# CH32F203RBT6-R0.net
KiCad netlist of a schematic drawn in Altium Designer
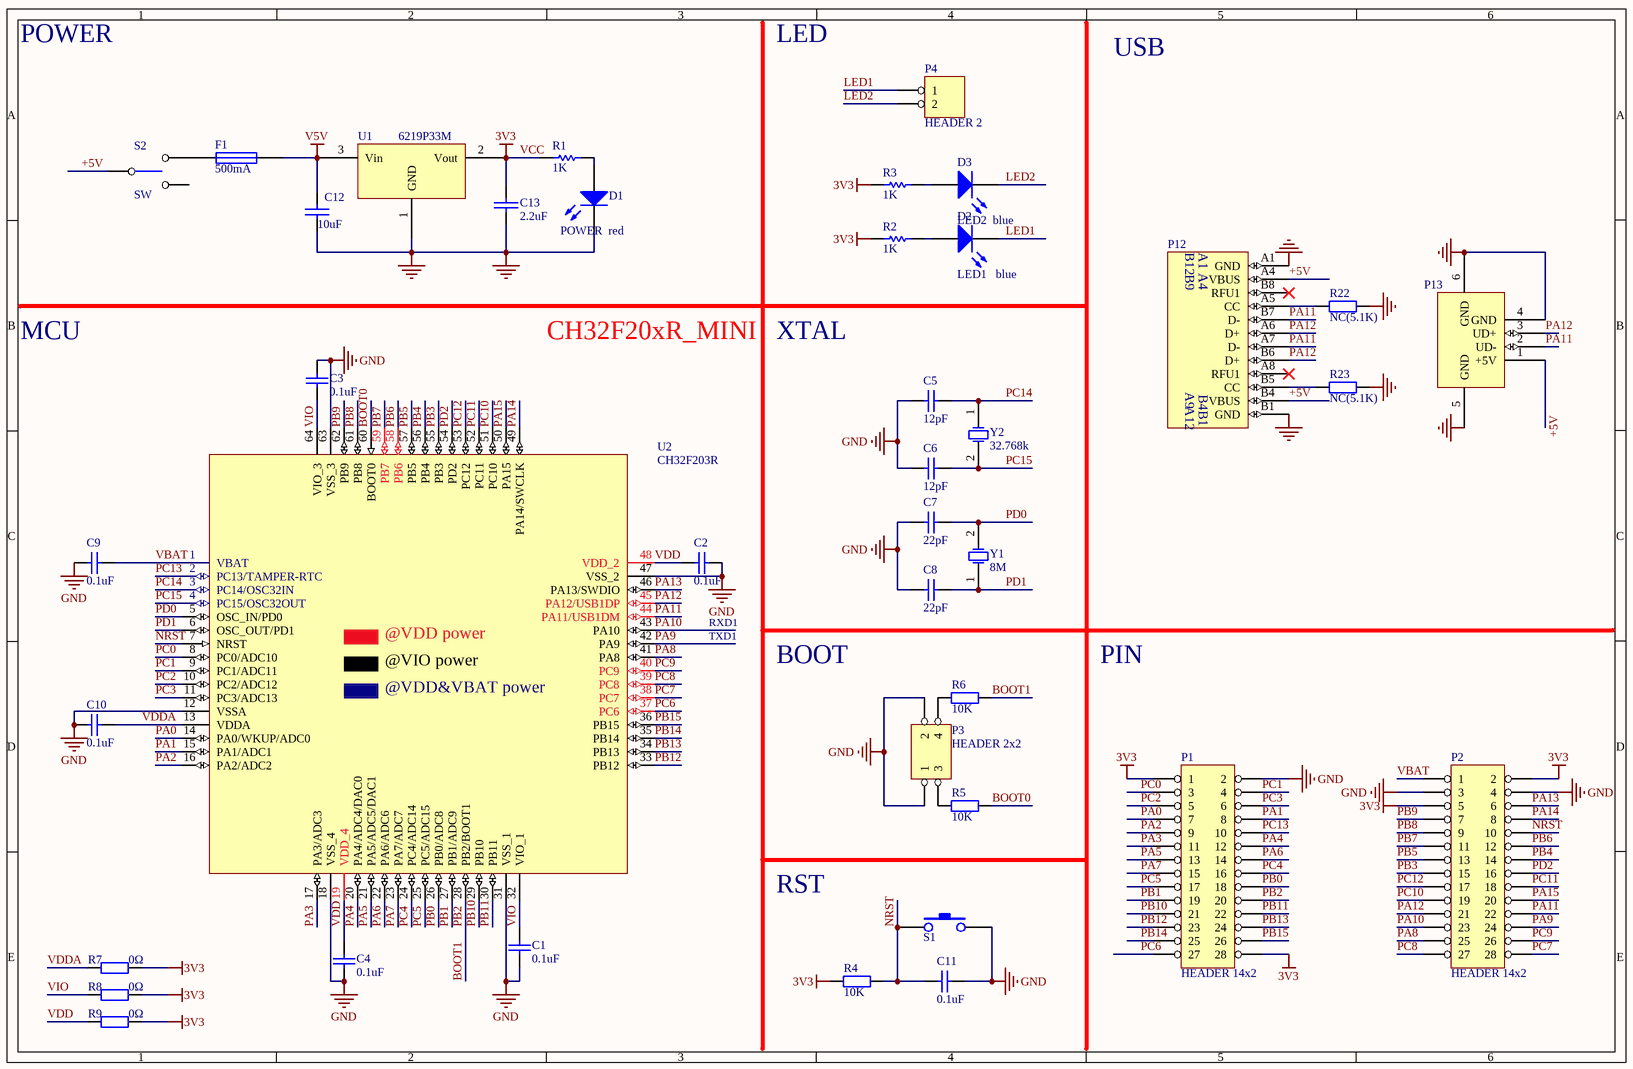
[diagram p0: CH32F203RBT6-R0.SchDoc]

(export (version "E")
  (design (tool "Eeschema 10.0.6"))
  (components
    (comp (ref "C1")
      (value "0.1uF")
      (footprint "0603_C")
      (description "Capacitor")
      (fields (field (name "PUBLISHER") "Altium Limited"))
      (libsource (lib "Miscellaneous Devices") (part "Cap"))
    )
    (comp (ref "C2")
      (value "0.1uF")
      (footprint "0603_C")
      (description "Capacitor")
      (fields (field (name "PUBLISHER") "Altium Limited"))
      (libsource (lib "Miscellaneous Devices") (part "Cap"))
    )
    (comp (ref "C3")
      (value "0.1uF")
      (footprint "0603_C")
      (description "Capacitor")
      (fields (field (name "PUBLISHER") "Altium Limited"))
      (libsource (lib "Miscellaneous Devices") (part "Cap"))
    )
    (comp (ref "C4")
      (value "0.1uF")
      (footprint "0603_C")
      (description "Capacitor")
      (fields (field (name "PUBLISHER") "Altium Limited"))
      (libsource (lib "Miscellaneous Devices") (part "Cap"))
    )
    (comp (ref "C5")
      (value "12pF")
      (footprint "0603_C")
      (description "Capacitor")
      (fields (field (name "PUBLISHER") "Altium Limited"))
      (libsource (lib "Miscellaneous Devices") (part "Cap"))
    )
    (comp (ref "C6")
      (value "12pF")
      (footprint "0603_C")
      (description "Capacitor")
      (fields (field (name "PUBLISHER") "Altium Limited"))
      (libsource (lib "Miscellaneous Devices") (part "Cap"))
    )
    (comp (ref "C7")
      (value "22pF")
      (footprint "0603_C")
      (description "Capacitor")
      (fields (field (name "PUBLISHER") "Altium Limited"))
      (libsource (lib "Miscellaneous Devices") (part "Cap"))
    )
    (comp (ref "C8")
      (value "22pF")
      (footprint "0603_C")
      (description "Capacitor")
      (fields (field (name "PUBLISHER") "Altium Limited"))
      (libsource (lib "Miscellaneous Devices") (part "Cap"))
    )
    (comp (ref "C9")
      (value "0.1uF")
      (footprint "0603_C")
      (description "Capacitor")
      (fields (field (name "PUBLISHER") "Altium Limited"))
      (libsource (lib "Miscellaneous Devices") (part "Cap"))
    )
    (comp (ref "C10")
      (value "0.1uF")
      (footprint "0603_C")
      (description "Capacitor")
      (fields (field (name "PUBLISHER") "Altium Limited"))
      (libsource (lib "Miscellaneous Devices") (part "Cap"))
    )
    (comp (ref "C11")
      (value "0.1uF")
      (footprint "0603_C")
      (description "Capacitor")
      (fields (field (name "PUBLISHER") "Altium Limited"))
      (libsource (lib "Miscellaneous Devices") (part "Cap"))
    )
    (comp (ref "C12")
      (value "10uF")
      (footprint "3216_C")
      (description "Capacitor")
      (libsource (lib "*") (part "CAP"))
    )
    (comp (ref "C13")
      (value "2.2uF")
      (footprint "0603_C")
      (description "Capacitor")
      (libsource (lib "*") (part "CAP"))
    )
    (comp (ref "D1")
      (value "POWER  red")
      (footprint "0603+")
      (description "Typical INFRARED GaAs LED")
      (fields (field (name "PUBLISHER") "Altium Limited"))
      (libsource (lib "Miscellaneous Devices") (part "LED0"))
    )
    (comp (ref "D2")
      (value "LED1   blue")
      (footprint "0603+")
      (description "Typical INFRARED GaAs LED")
      (fields (field (name "PUBLISHER") "Altium Limited"))
      (libsource (lib "Miscellaneous Devices") (part "LED0"))
    )
    (comp (ref "D3")
      (value "LED2  blue")
      (footprint "0603+")
      (description "Typical INFRARED GaAs LED")
      (fields (field (name "PUBLISHER") "Altium Limited"))
      (libsource (lib "Miscellaneous Devices") (part "LED0"))
    )
    (comp (ref "F1")
      (value "500mA")
      (footprint "0603")
      (description "Fuse")
      (libsource (lib "*") (part "FUSE1"))
    )
    (comp (ref "P1")
      (value "HEADER 14x2")
      (footprint "MYPCB:IDC28-2.54MM")
      (description "Header, 14-Pin, Dual row")
      (libsource (lib "wch_sch_others") (part "HEADER 14x2"))
    )
    (comp (ref "P2")
      (value "HEADER 14x2")
      (footprint "MYPCB:IDC28-2.54MM")
      (description "Header, 14-Pin, Dual row")
      (libsource (lib "wch_sch_others") (part "HEADER 14x2"))
    )
    (comp (ref "P3")
      (value "HEADER 2x2")
      (footprint "MYPCB:IDC4-2.54MM")
      (description "Header, 2-Pin, Dual row")
      (libsource (lib "wch_sch_others") (part "HEADER 2x2"))
    )
    (comp (ref "P4")
      (value "HEADER 2")
      (footprint "MYPCB:SIP2-2.54mm")
      (description "Header, 2-Pin")
      (libsource (lib "wch_sch_others") (part "HEADER 2"))
    )
    (comp (ref "P12")
      (value "TYPE-C")
      (footprint "TYPE-C-Receptacle-2.0")
      (libsource (lib "*") (part "TYPE-C1"))
    )
    (comp (ref "P13")
      (value "USB_A")
      (footprint "USBAF")
      (description "USB Port")
      (libsource (lib "CHXXXSCH") (part "USB"))
    )
    (comp (ref "R1")
      (value "1K")
      (footprint "0603")
      (description "Semiconductor Resistor")
      (fields (field (name "PUBLISHER") "Altium Limited"))
      (libsource (lib "Miscellaneous Devices") (part "Res Semi"))
    )
    (comp (ref "R2")
      (value "1K")
      (footprint "0603")
      (description "Semiconductor Resistor")
      (fields (field (name "PUBLISHER") "Altium Limited"))
      (libsource (lib "Miscellaneous Devices") (part "Res Semi"))
    )
    (comp (ref "R3")
      (value "1K")
      (footprint "0603")
      (description "Semiconductor Resistor")
      (fields (field (name "PUBLISHER") "Altium Limited"))
      (libsource (lib "Miscellaneous Devices") (part "Res Semi"))
    )
    (comp (ref "R4")
      (value "10K")
      (footprint "0603")
      (description "Resistor")
      (fields (field (name "PUBLISHER") "Altium Limited"))
      (libsource (lib "Miscellaneous Devices") (part "Res2"))
    )
    (comp (ref "R5")
      (value "10K")
      (footprint "0603")
      (description "Resistor")
      (fields (field (name "PUBLISHER") "Altium Limited"))
      (libsource (lib "Miscellaneous Devices") (part "Res2"))
    )
    (comp (ref "R6")
      (value "10K")
      (footprint "0603")
      (description "Resistor")
      (fields (field (name "PUBLISHER") "Altium Limited"))
      (libsource (lib "Miscellaneous Devices") (part "Res2"))
    )
    (comp (ref "R7")
      (value "0Ω")
      (footprint "0603")
      (description "Resistor")
      (fields (field (name "PUBLISHER") "Altium Limited"))
      (libsource (lib "Miscellaneous Devices") (part "Res2"))
    )
    (comp (ref "R8")
      (value "0Ω")
      (footprint "0603")
      (description "Resistor")
      (fields (field (name "PUBLISHER") "Altium Limited"))
      (libsource (lib "Miscellaneous Devices") (part "Res2"))
    )
    (comp (ref "R9")
      (value "0Ω")
      (footprint "0603")
      (description "Resistor")
      (fields (field (name "PUBLISHER") "Altium Limited"))
      (libsource (lib "Miscellaneous Devices") (part "Res2"))
    )
    (comp (ref "R22")
      (value "NC(5.1K)")
      (footprint "0603")
      (description "Resistor")
      (libsource (lib "") (part "Res2_1"))
    )
    (comp (ref "R23")
      (value "NC(5.1K)")
      (footprint "0603")
      (description "Resistor")
      (libsource (lib "") (part "Res2_1"))
    )
    (comp (ref "S1")
      (value "RST")
      (footprint "SMD_6.1x3.65x2.5mm-KEY")
      (libsource (lib "CCDXPLIB") (part "KEY"))
    )
    (comp (ref "S2") (value "SW") (footprint "KEY2") (libsource (lib "MYSCH") (part "SW")))
    (comp (ref "U1")
      (value "6219P33M")
      (footprint "SOT-23")
      (libsource (lib "wch_sch_others") (part "6219P33M"))
    )
    (comp (ref "U2")
      (value "CH32F203R")
      (footprint "LQFP64M_10x10")
      (description "ARM M3 HD-MCU, 144MHz, 8*UART, 10*Timer, 4*OPA")
      (libsource (lib "CHXXX") (part "CH32F203R"))
    )
    (comp (ref "Y1")
      (value "8M")
      (footprint "XT_AT49")
      (description "Crystal Oscillator")
      (fields (field (name "PUBLISHER") "Altium Limited"))
      (libsource (lib "Miscellaneous Devices") (part "XTAL"))
    )
    (comp (ref "Y2")
      (value "32.768k")
      (footprint "FC-135")
      (description "Crystal Oscillator")
      (fields (field (name "PUBLISHER") "Altium Limited"))
      (libsource (lib "Miscellaneous Devices") (part "XTAL"))
    )
  )
  (nets
    (net (code "1") (name "/+5V") (class "Default")
      (node (ref "P12") (pin "A4") (pinfunction "VBUS_A4") (pintype "bidirectional"))
      (node (ref "P12") (pin "B4") (pinfunction "VBUS_B4") (pintype "bidirectional"))
      (node (ref "P13") (pin "1") (pinfunction "+5V_1") (pintype "power_in"))
      (node (ref "S2") (pin "1") (pinfunction "1_1") (pintype "passive"))
    )
    (net (code "3") (name "/BOOT0") (class "Default")
      (node (ref "R5") (pin "1") (pinfunction "1_1") (pintype "passive"))
      (node (ref "U2") (pin "60") (pinfunction "BOOT0_60") (pintype "input"))
    )
    (net (code "4") (name "/BOOT1") (class "Default")
      (node (ref "P1") (pin "20") (pinfunction "20_20") (pintype "passive"))
      (node (ref "R6") (pin "1") (pinfunction "1_1") (pintype "passive"))
      (node (ref "U2") (pin "28") (pinfunction "PB2/BOOT1_28") (pintype "bidirectional"))
    )
    (net (code "5") (name "/LED1") (class "Default")
      (node (ref "D2") (pin "2") (pinfunction "K_2") (pintype "passive"))
      (node (ref "P4") (pin "1") (pinfunction "1_1") (pintype "passive"))
    )
    (net (code "6") (name "/LED2") (class "Default")
      (node (ref "D3") (pin "2") (pinfunction "K_2") (pintype "passive"))
      (node (ref "P4") (pin "2") (pinfunction "2_2") (pintype "passive"))
    )
    (net (code "7") (name "/NRST") (class "Default")
      (node (ref "C11") (pin "2") (pinfunction "2_2") (pintype "passive"))
      (node (ref "P2") (pin "10") (pinfunction "10_10") (pintype "passive"))
      (node (ref "R4") (pin "1") (pinfunction "1_1") (pintype "passive"))
      (node (ref "S1") (pin "1") (pinfunction "1_1") (pintype "passive"))
      (node (ref "U2") (pin "7") (pinfunction "NRST_7") (pintype "input"))
    )
    (net (code "8") (name "/PA0") (class "Default")
      (node (ref "P1") (pin "7") (pinfunction "7_7") (pintype "passive"))
      (node (ref "U2") (pin "14") (pinfunction "PA0/WKUP/ADC0_14") (pintype "bidirectional"))
    )
    (net (code "9") (name "/PA1") (class "Default")
      (node (ref "P1") (pin "8") (pinfunction "8_8") (pintype "passive"))
      (node (ref "U2") (pin "15") (pinfunction "PA1/ADC1_15") (pintype "bidirectional"))
    )
    (net (code "10") (name "/PA2") (class "Default")
      (node (ref "P1") (pin "9") (pinfunction "9_9") (pintype "passive"))
      (node (ref "U2") (pin "16") (pinfunction "PA2/ADC2_16") (pintype "bidirectional"))
    )
    (net (code "11") (name "/PA3") (class "Default")
      (node (ref "P1") (pin "11") (pinfunction "11_11") (pintype "passive"))
      (node (ref "U2") (pin "17") (pinfunction "PA3/ADC3_17") (pintype "bidirectional"))
    )
    (net (code "12") (name "/PA4") (class "Default")
      (node (ref "P1") (pin "12") (pinfunction "12_12") (pintype "passive"))
      (node (ref "U2") (pin "20") (pinfunction "PA4/ADC4/DAC0_20") (pintype "bidirectional"))
    )
    (net (code "13") (name "/PA5") (class "Default")
      (node (ref "P1") (pin "13") (pinfunction "13_13") (pintype "passive"))
      (node (ref "U2") (pin "21") (pinfunction "PA5/ADC5/DAC1_21") (pintype "bidirectional"))
    )
    (net (code "14") (name "/PA6") (class "Default")
      (node (ref "P1") (pin "14") (pinfunction "14_14") (pintype "passive"))
      (node (ref "U2") (pin "22") (pinfunction "PA6/ADC6_22") (pintype "bidirectional"))
    )
    (net (code "15") (name "/PA7") (class "Default")
      (node (ref "P1") (pin "15") (pinfunction "15_15") (pintype "passive"))
      (node (ref "U2") (pin "23") (pinfunction "PA7/ADC7_23") (pintype "bidirectional"))
    )
    (net (code "16") (name "/PA8") (class "Default")
      (node (ref "P2") (pin "25") (pinfunction "25_25") (pintype "passive"))
      (node (ref "U2") (pin "41") (pinfunction "PA8_41") (pintype "bidirectional"))
    )
    (net (code "17") (name "/PA9") (class "Default")
      (node (ref "P2") (pin "24") (pinfunction "24_24") (pintype "passive"))
      (node (ref "U2") (pin "42") (pinfunction "PA9_42") (pintype "bidirectional"))
    )
    (net (code "18") (name "/PA10") (class "Default")
      (node (ref "P2") (pin "23") (pinfunction "23_23") (pintype "passive"))
      (node (ref "U2") (pin "43") (pinfunction "PA10_43") (pintype "bidirectional"))
    )
    (net (code "19") (name "/PA11") (class "Default")
      (node (ref "P12") (pin "A7") (pinfunction "D-_A7") (pintype "bidirectional"))
      (node (ref "P12") (pin "B7") (pinfunction "D-_B7") (pintype "bidirectional"))
      (node (ref "P13") (pin "2") (pinfunction "UD-_2") (pintype "bidirectional"))
      (node (ref "P2") (pin "22") (pinfunction "22_22") (pintype "passive"))
      (node (ref "U2") (pin "44") (pinfunction "PA11/USB1DM_44") (pintype "bidirectional"))
    )
    (net (code "20") (name "/PA12") (class "Default")
      (node (ref "P12") (pin "A6") (pinfunction "D+_A6") (pintype "bidirectional"))
      (node (ref "P12") (pin "B6") (pinfunction "D+_B6") (pintype "bidirectional"))
      (node (ref "P13") (pin "3") (pinfunction "UD+_3") (pintype "bidirectional"))
      (node (ref "P2") (pin "21") (pinfunction "21_21") (pintype "passive"))
      (node (ref "U2") (pin "45") (pinfunction "PA12/USB1DP_45") (pintype "bidirectional"))
    )
    (net (code "21") (name "/PA13") (class "Default")
      (node (ref "P2") (pin "6") (pinfunction "6_6") (pintype "passive"))
      (node (ref "U2") (pin "46") (pinfunction "PA13/SWDIO_46") (pintype "bidirectional"))
    )
    (net (code "22") (name "/PA14") (class "Default")
      (node (ref "P2") (pin "8") (pinfunction "8_8") (pintype "passive"))
      (node (ref "U2") (pin "49") (pinfunction "PA14/SWCLK_49") (pintype "bidirectional"))
    )
    (net (code "23") (name "/PA15") (class "Default")
      (node (ref "P2") (pin "20") (pinfunction "20_20") (pintype "passive"))
      (node (ref "U2") (pin "50") (pinfunction "PA15_50") (pintype "bidirectional"))
    )
    (net (code "24") (name "/PB0") (class "Default")
      (node (ref "P1") (pin "18") (pinfunction "18_18") (pintype "passive"))
      (node (ref "U2") (pin "26") (pinfunction "PB0/ADC8_26") (pintype "bidirectional"))
    )
    (net (code "25") (name "/PB1") (class "Default")
      (node (ref "P1") (pin "19") (pinfunction "19_19") (pintype "passive"))
      (node (ref "U2") (pin "27") (pinfunction "PB1/ADC9_27") (pintype "bidirectional"))
    )
    (net (code "26") (name "/PB3") (class "Default")
      (node (ref "P2") (pin "15") (pinfunction "15_15") (pintype "passive"))
      (node (ref "U2") (pin "55") (pinfunction "PB3_55") (pintype "bidirectional"))
    )
    (net (code "27") (name "/PB4") (class "Default")
      (node (ref "P2") (pin "14") (pinfunction "14_14") (pintype "passive"))
      (node (ref "U2") (pin "56") (pinfunction "PB4_56") (pintype "bidirectional"))
    )
    (net (code "28") (name "/PB5") (class "Default")
      (node (ref "P2") (pin "13") (pinfunction "13_13") (pintype "passive"))
      (node (ref "U2") (pin "57") (pinfunction "PB5_57") (pintype "bidirectional"))
    )
    (net (code "29") (name "/PB6") (class "Default")
      (node (ref "P2") (pin "12") (pinfunction "12_12") (pintype "passive"))
      (node (ref "U2") (pin "58") (pinfunction "PB6_58") (pintype "bidirectional"))
    )
    (net (code "30") (name "/PB7") (class "Default")
      (node (ref "P2") (pin "11") (pinfunction "11_11") (pintype "passive"))
      (node (ref "U2") (pin "59") (pinfunction "PB7_59") (pintype "bidirectional"))
    )
    (net (code "31") (name "/PB8") (class "Default")
      (node (ref "P2") (pin "9") (pinfunction "9_9") (pintype "passive"))
      (node (ref "U2") (pin "61") (pinfunction "PB8_61") (pintype "bidirectional"))
    )
    (net (code "32") (name "/PB9") (class "Default")
      (node (ref "P2") (pin "7") (pinfunction "7_7") (pintype "passive"))
      (node (ref "U2") (pin "62") (pinfunction "PB9_62") (pintype "bidirectional"))
    )
    (net (code "33") (name "/PB10") (class "Default")
      (node (ref "P1") (pin "21") (pinfunction "21_21") (pintype "passive"))
      (node (ref "U2") (pin "29") (pinfunction "PB10_29") (pintype "bidirectional"))
    )
    (net (code "34") (name "/PB11") (class "Default")
      (node (ref "P1") (pin "22") (pinfunction "22_22") (pintype "passive"))
      (node (ref "U2") (pin "30") (pinfunction "PB11_30") (pintype "bidirectional"))
    )
    (net (code "35") (name "/PB12") (class "Default")
      (node (ref "P1") (pin "23") (pinfunction "23_23") (pintype "passive"))
      (node (ref "U2") (pin "33") (pinfunction "PB12_33") (pintype "bidirectional"))
    )
    (net (code "36") (name "/PB13") (class "Default")
      (node (ref "P1") (pin "24") (pinfunction "24_24") (pintype "passive"))
      (node (ref "U2") (pin "34") (pinfunction "PB13_34") (pintype "bidirectional"))
    )
    (net (code "37") (name "/PB14") (class "Default")
      (node (ref "P1") (pin "25") (pinfunction "25_25") (pintype "passive"))
      (node (ref "U2") (pin "35") (pinfunction "PB14_35") (pintype "bidirectional"))
    )
    (net (code "38") (name "/PB15") (class "Default")
      (node (ref "P1") (pin "26") (pinfunction "26_26") (pintype "passive"))
      (node (ref "U2") (pin "36") (pinfunction "PB15_36") (pintype "bidirectional"))
    )
    (net (code "39") (name "/PC0") (class "Default")
      (node (ref "P1") (pin "3") (pinfunction "3_3") (pintype "passive"))
      (node (ref "U2") (pin "8") (pinfunction "PC0/ADC10_8") (pintype "bidirectional"))
    )
    (net (code "40") (name "/PC1") (class "Default")
      (node (ref "P1") (pin "4") (pinfunction "4_4") (pintype "passive"))
      (node (ref "U2") (pin "9") (pinfunction "PC1/ADC11_9") (pintype "bidirectional"))
    )
    (net (code "41") (name "/PC2") (class "Default")
      (node (ref "P1") (pin "5") (pinfunction "5_5") (pintype "passive"))
      (node (ref "U2") (pin "10") (pinfunction "PC2/ADC12_10") (pintype "bidirectional"))
    )
    (net (code "42") (name "/PC3") (class "Default")
      (node (ref "P1") (pin "6") (pinfunction "6_6") (pintype "passive"))
      (node (ref "U2") (pin "11") (pinfunction "PC3/ADC13_11") (pintype "bidirectional"))
    )
    (net (code "43") (name "/PC4") (class "Default")
      (node (ref "P1") (pin "16") (pinfunction "16_16") (pintype "passive"))
      (node (ref "U2") (pin "24") (pinfunction "PC4/ADC14_24") (pintype "bidirectional"))
    )
    (net (code "44") (name "/PC5") (class "Default")
      (node (ref "P1") (pin "17") (pinfunction "17_17") (pintype "passive"))
      (node (ref "U2") (pin "25") (pinfunction "PC5/ADC15_25") (pintype "bidirectional"))
    )
    (net (code "45") (name "/PC6") (class "Default")
      (node (ref "P1") (pin "27") (pinfunction "27_27") (pintype "passive"))
      (node (ref "U2") (pin "37") (pinfunction "PC6_37") (pintype "bidirectional"))
    )
    (net (code "46") (name "/PC7") (class "Default")
      (node (ref "P2") (pin "28") (pinfunction "28_28") (pintype "passive"))
      (node (ref "U2") (pin "38") (pinfunction "PC7_38") (pintype "bidirectional"))
    )
    (net (code "47") (name "/PC8") (class "Default")
      (node (ref "P2") (pin "27") (pinfunction "27_27") (pintype "passive"))
      (node (ref "U2") (pin "39") (pinfunction "PC8_39") (pintype "bidirectional"))
    )
    (net (code "48") (name "/PC9") (class "Default")
      (node (ref "P2") (pin "26") (pinfunction "26_26") (pintype "passive"))
      (node (ref "U2") (pin "40") (pinfunction "PC9_40") (pintype "bidirectional"))
    )
    (net (code "49") (name "/PC10") (class "Default")
      (node (ref "P2") (pin "19") (pinfunction "19_19") (pintype "passive"))
      (node (ref "U2") (pin "51") (pinfunction "PC10_51") (pintype "bidirectional"))
    )
    (net (code "50") (name "/PC11") (class "Default")
      (node (ref "P2") (pin "18") (pinfunction "18_18") (pintype "passive"))
      (node (ref "U2") (pin "52") (pinfunction "PC11_52") (pintype "bidirectional"))
    )
    (net (code "51") (name "/PC12") (class "Default")
      (node (ref "P2") (pin "17") (pinfunction "17_17") (pintype "passive"))
      (node (ref "U2") (pin "53") (pinfunction "PC12_53") (pintype "bidirectional"))
    )
    (net (code "52") (name "/PC13") (class "Default")
      (node (ref "P1") (pin "10") (pinfunction "10_10") (pintype "passive"))
      (node (ref "U2") (pin "2") (pinfunction "PC13/TAMPER-RTC_2") (pintype "bidirectional"))
    )
    (net (code "53") (name "/PC14") (class "Default")
      (node (ref "C5") (pin "1") (pinfunction "1_1") (pintype "passive"))
      (node (ref "U2") (pin "3") (pinfunction "PC14/OSC32IN_3") (pintype "bidirectional"))
      (node (ref "Y2") (pin "1") (pinfunction "OSC1_1") (pintype "passive"))
    )
    (net (code "54") (name "/PC15") (class "Default")
      (node (ref "C6") (pin "1") (pinfunction "1_1") (pintype "passive"))
      (node (ref "U2") (pin "4") (pinfunction "PC15/OSC32OUT_4") (pintype "bidirectional"))
      (node (ref "Y2") (pin "2") (pinfunction "OSC2_2") (pintype "passive"))
    )
    (net (code "55") (name "/PD0") (class "Default")
      (node (ref "C7") (pin "2") (pinfunction "2_2") (pintype "passive"))
      (node (ref "U2") (pin "5") (pinfunction "OSC_IN/PD0_5") (pintype "bidirectional"))
      (node (ref "Y1") (pin "2") (pinfunction "OSC2_2") (pintype "passive"))
    )
    (net (code "56") (name "/PD1") (class "Default")
      (node (ref "C8") (pin "2") (pinfunction "2_2") (pintype "passive"))
      (node (ref "U2") (pin "6") (pinfunction "OSC_OUT/PD1_6") (pintype "bidirectional"))
      (node (ref "Y1") (pin "1") (pinfunction "OSC1_1") (pintype "passive"))
    )
    (net (code "57") (name "/PD2") (class "Default")
      (node (ref "P2") (pin "16") (pinfunction "16_16") (pintype "passive"))
      (node (ref "U2") (pin "54") (pinfunction "PD2_54") (pintype "bidirectional"))
    )
    (net (code "58") (name "/VBAT") (class "Default")
      (node (ref "C9") (pin "1") (pinfunction "1_1") (pintype "passive"))
      (node (ref "P2") (pin "1") (pinfunction "1_1") (pintype "passive"))
      (node (ref "U2") (pin "1") (pinfunction "VBAT_1") (pintype "power_in"))
    )
    (net (code "59") (name "/VDD") (class "Default")
      (node (ref "C2") (pin "2") (pinfunction "2_2") (pintype "passive"))
      (node (ref "C4") (pin "2") (pinfunction "2_2") (pintype "passive"))
      (node (ref "R9") (pin "2") (pinfunction "2_2") (pintype "passive"))
      (node (ref "U2") (pin "19") (pinfunction "VDD_4_19") (pintype "power_in"))
      (node (ref "U2") (pin "48") (pinfunction "VDD_2_48") (pintype "power_in"))
    )
    (net (code "60") (name "/VDDA") (class "Default")
      (node (ref "C10") (pin "1") (pinfunction "1_1") (pintype "passive"))
      (node (ref "R7") (pin "2") (pinfunction "2_2") (pintype "passive"))
      (node (ref "U2") (pin "13") (pinfunction "VDDA_13") (pintype "power_in"))
    )
    (net (code "61") (name "/VIO") (class "Default")
      (node (ref "C1") (pin "2") (pinfunction "2_2") (pintype "passive"))
      (node (ref "C3") (pin "2") (pinfunction "2_2") (pintype "passive"))
      (node (ref "R8") (pin "2") (pinfunction "2_2") (pintype "passive"))
      (node (ref "U2") (pin "32") (pinfunction "VIO_1_32") (pintype "power_in"))
      (node (ref "U2") (pin "64") (pinfunction "VIO_3_64") (pintype "power_in"))
    )
    (net (code "62") (name "3V3") (class "Default")
      (node (ref "C13") (pin "1") (pinfunction "1_1") (pintype "passive"))
      (node (ref "P1") (pin "1") (pinfunction "1_1") (pintype "passive"))
      (node (ref "P1") (pin "28") (pinfunction "28_28") (pintype "passive"))
      (node (ref "P2") (pin "2") (pinfunction "2_2") (pintype "passive"))
      (node (ref "P2") (pin "5") (pinfunction "5_5") (pintype "passive"))
      (node (ref "R1") (pin "2") (pinfunction "2_2") (pintype "passive"))
      (node (ref "R2") (pin "1") (pinfunction "1_1") (pintype "passive"))
      (node (ref "R3") (pin "1") (pinfunction "1_1") (pintype "passive"))
      (node (ref "R4") (pin "2") (pinfunction "2_2") (pintype "passive"))
      (node (ref "R7") (pin "1") (pinfunction "1_1") (pintype "passive"))
      (node (ref "R8") (pin "1") (pinfunction "1_1") (pintype "passive"))
      (node (ref "R9") (pin "1") (pinfunction "1_1") (pintype "passive"))
      (node (ref "U1") (pin "2") (pinfunction "Vout_2") (pintype "passive"))
    )
    (net (code "63") (name "GND") (class "Default")
      (node (ref "C1") (pin "1") (pinfunction "1_1") (pintype "passive"))
      (node (ref "C10") (pin "2") (pinfunction "2_2") (pintype "passive"))
      (node (ref "C11") (pin "1") (pinfunction "1_1") (pintype "passive"))
      (node (ref "C12") (pin "2") (pinfunction "2_2") (pintype "passive"))
      (node (ref "C13") (pin "2") (pinfunction "2_2") (pintype "passive"))
      (node (ref "C2") (pin "1") (pinfunction "1_1") (pintype "passive"))
      (node (ref "C3") (pin "1") (pinfunction "1_1") (pintype "passive"))
      (node (ref "C4") (pin "1") (pinfunction "1_1") (pintype "passive"))
      (node (ref "C5") (pin "2") (pinfunction "2_2") (pintype "passive"))
      (node (ref "C6") (pin "2") (pinfunction "2_2") (pintype "passive"))
      (node (ref "C7") (pin "1") (pinfunction "1_1") (pintype "passive"))
      (node (ref "C8") (pin "1") (pinfunction "1_1") (pintype "passive"))
      (node (ref "C9") (pin "2") (pinfunction "2_2") (pintype "passive"))
      (node (ref "D1") (pin "2") (pinfunction "K_2") (pintype "passive"))
      (node (ref "P1") (pin "2") (pinfunction "2_2") (pintype "passive"))
      (node (ref "P12") (pin "A1") (pinfunction "GND_A1") (pintype "bidirectional"))
      (node (ref "P12") (pin "B1") (pinfunction "GND_B1") (pintype "bidirectional"))
      (node (ref "P13") (pin "4") (pinfunction "GND_4") (pintype "power_in"))
      (node (ref "P13") (pin "5") (pinfunction "GND_5") (pintype "power_in"))
      (node (ref "P13") (pin "6") (pinfunction "GND_6") (pintype "power_in"))
      (node (ref "P2") (pin "3") (pinfunction "3_3") (pintype "passive"))
      (node (ref "P2") (pin "4") (pinfunction "4_4") (pintype "passive"))
      (node (ref "P3") (pin "1") (pinfunction "1_1") (pintype "passive"))
      (node (ref "P3") (pin "2") (pinfunction "2_2") (pintype "passive"))
      (node (ref "R22") (pin "2") (pinfunction "2_2") (pintype "passive"))
      (node (ref "R23") (pin "2") (pinfunction "2_2") (pintype "passive"))
      (node (ref "S1") (pin "2") (pinfunction "2_2") (pintype "passive"))
      (node (ref "U1") (pin "1") (pinfunction "GND_1") (pintype "passive"))
      (node (ref "U2") (pin "12") (pinfunction "VSSA_12") (pintype "power_in"))
      (node (ref "U2") (pin "18") (pinfunction "VSS_4_18") (pintype "power_in"))
      (node (ref "U2") (pin "31") (pinfunction "VSS_1_31") (pintype "power_in"))
      (node (ref "U2") (pin "47") (pinfunction "VSS_2_47") (pintype "power_in"))
      (node (ref "U2") (pin "63") (pinfunction "VSS_3_63") (pintype "power_in"))
    )
    (net (code "64") (name "Net-(D1-A)") (class "Default")
      (node (ref "D1") (pin "1") (pinfunction "A_1") (pintype "passive"))
      (node (ref "R1") (pin "1") (pinfunction "1_1") (pintype "passive"))
    )
    (net (code "65") (name "Net-(D2-A)") (class "Default")
      (node (ref "D2") (pin "1") (pinfunction "A_1") (pintype "passive"))
      (node (ref "R2") (pin "2") (pinfunction "2_2") (pintype "passive"))
    )
    (net (code "66") (name "Net-(D3-A)") (class "Default")
      (node (ref "D3") (pin "1") (pinfunction "A_1") (pintype "passive"))
      (node (ref "R3") (pin "2") (pinfunction "2_2") (pintype "passive"))
    )
    (net (code "67") (name "Net-(F1-Pad1)") (class "Default")
      (node (ref "F1") (pin "1") (pinfunction "1_1") (pintype "passive"))
      (node (ref "S2") (pin "3") (pinfunction "3_3") (pintype "passive"))
    )
    (net (code "68") (name "Net-(P3-Pad3)") (class "Default")
      (node (ref "P3") (pin "3") (pinfunction "3_3") (pintype "passive"))
      (node (ref "R5") (pin "2") (pinfunction "2_2") (pintype "passive"))
    )
    (net (code "69") (name "Net-(P3-Pad4)") (class "Default")
      (node (ref "P3") (pin "4") (pinfunction "4_4") (pintype "passive"))
      (node (ref "R6") (pin "2") (pinfunction "2_2") (pintype "passive"))
    )
    (net (code "70") (name "Net-(P12-CC-PadA5)") (class "Default")
      (node (ref "P12") (pin "A5") (pinfunction "CC_A5") (pintype "bidirectional"))
      (node (ref "R22") (pin "1") (pinfunction "1_1") (pintype "passive"))
    )
    (net (code "71") (name "Net-(P12-CC-PadB5)") (class "Default")
      (node (ref "P12") (pin "B5") (pinfunction "CC_B5") (pintype "bidirectional"))
      (node (ref "R23") (pin "1") (pinfunction "1_1") (pintype "passive"))
    )
    (net (code "72") (name "V5V") (class "Default")
      (node (ref "C12") (pin "1") (pinfunction "1_1") (pintype "passive"))
      (node (ref "F1") (pin "2") (pinfunction "2_2") (pintype "passive"))
      (node (ref "U1") (pin "3") (pinfunction "Vin_3") (pintype "passive"))
    )
    (net (code "73") (name "unconnected-(P12-RFU1-PadA8)") (class "Default")
      (node (ref "P12") (pin "A8") (pinfunction "RFU1_A8") (pintype "bidirectional+no_connect"))
    )
    (net (code "74") (name "unconnected-(P12-RFU1-PadB8)") (class "Default")
      (node (ref "P12") (pin "B8") (pinfunction "RFU1_B8") (pintype "bidirectional+no_connect"))
    )
    (net (code "75") (name "unconnected-(S2-Pad2)") (class "Default")
      (node (ref "S2") (pin "2") (pinfunction "2_2") (pintype "passive"))
    )
  )
)
